# Connectors.net
KiCad netlist of a schematic drawn in Altium Designer
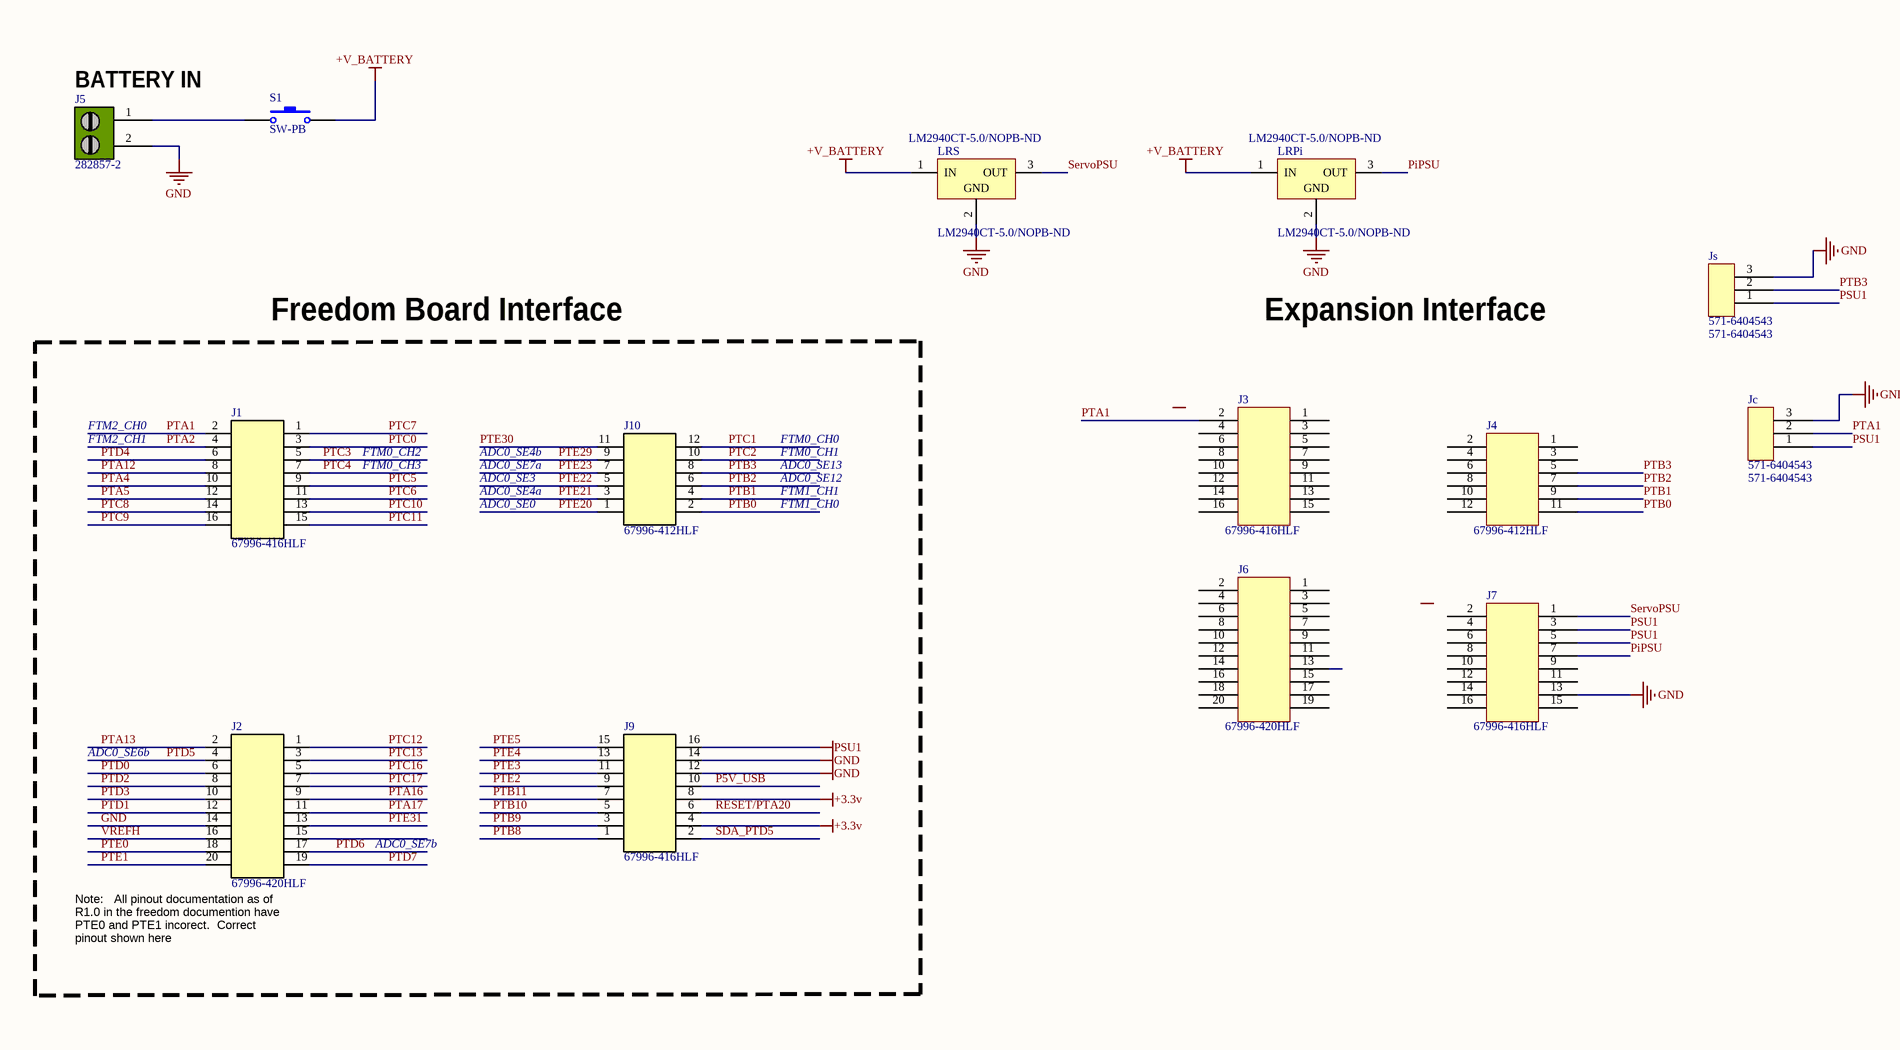
[diagram p0: Connectors.SchDoc, top left]
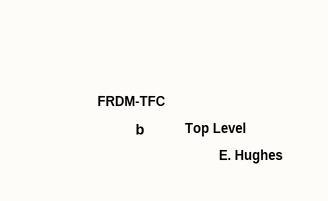
[diagram p1: Connectors.SchDoc, bottom right]

(export (version "E")
  (design (tool "Eeschema 10.0.6"))
  (components
    (comp (ref "J1")
      (value "67996-416HLF")
      (footprint "67996-416HLF")
      (description "CONN HEADER 16POS .100 STR TIN")
      (fields (field (name "MANUFACTURER") "FCI"))
      (libsource (lib "") (part "67996-416HLF_1"))
    )
    (comp (ref "J2")
      (value "67996-420HLF")
      (footprint "67996-420HLF")
      (description "CONN HEADER 20POS .100 STR TIN")
      (fields (field (name "MANUFACTURER") "FCI"))
      (libsource (lib "eConnector") (part "67996-420HLF"))
    )
    (comp (ref "J3")
      (value "67996-416HLF")
      (footprint "67996-416HLF")
      (description "CONN HEADER 16POS .100 STR TIN")
      (libsource (lib "Amphenol_Connectors") (part "67996-416HLF"))
    )
    (comp (ref "J4")
      (value "67996-412HLF")
      (footprint "67996-412HLF")
      (description "CONN HEADER 12POS .100 STR TIN")
      (libsource (lib "Amphenol_Connectors") (part "67996-412HLF"))
    )
    (comp (ref "J5")
      (value "282857-2")
      (footprint "282857-2")
      (description "TERM BLOCK 2POS SIDE ENT 5.08MM")
      (fields (field (name "MANUFACTURER") "TE Connectivity") (field (name "VOLTAGE") "300V"))
      (libsource (lib "eConnector") (part "282857-2"))
    )
    (comp (ref "J6")
      (value "67996-420HLF")
      (footprint "67996-420HLF")
      (description "CONN HEADER 20POS .100 STR TIN")
      (libsource (lib "Amphenol_Connectors") (part "67996-420HLF"))
    )
    (comp (ref "J7")
      (value "67996-416HLF")
      (footprint "67996-416HLF")
      (description "CONN HEADER 16POS .100 STR TIN")
      (libsource (lib "Amphenol_Connectors") (part "67996-416HLF"))
    )
    (comp (ref "J9")
      (value "67996-416HLF")
      (footprint "67996-416HLF")
      (description "CONN HEADER 16POS .100 STR TIN")
      (fields (field (name "MANUFACTURER") "FCI"))
      (libsource (lib "eConnector") (part "67996-416HLF"))
    )
    (comp (ref "J10")
      (value "67996-412HLF")
      (footprint "67996-412HLF")
      (description "CONN HEADER 12POS .100 STR TIN")
      (fields (field (name "MANUFACTURER") "FCI"))
      (libsource (lib "eConnector") (part "67996-412HLF"))
    )
    (comp (ref "Jc")
      (value "571-6404543")
      (footprint "6404543")
      (description "Headers & Wire Housings POLARIZED HEADER 3P Straight Post tin, Mouser")
      (fields (field (name "SUPPLIER PART NUMBER 1") "571-6404543"))
      (libsource (lib "TE_Connectors") (part "640454-3"))
    )
    (comp (ref "Js")
      (value "571-6404543")
      (footprint "6404543")
      (description "Headers & Wire Housings POLARIZED HEADER 3P Straight Post tin, Mouser")
      (fields (field (name "SUPPLIER PART NUMBER 1") "571-6404543"))
      (libsource (lib "TE_Connectors") (part "640454-3"))
    )
    (comp (ref "LRPi")
      (value "LM2940CT-5.0/NOPB-ND")
      (footprint "NDE0003A")
      (description "1A Low Dropout Regulator, 3-pin TO-220, Pb-Free, Digi-key")
      (fields
        (field (name "MANUFACTURER") "Texas Instruments")
        (field (name "SUPPLIER PART NUMBER 1") "LM2940CT-5.0/NOPB-ND")
      )
      (libsource (lib "Altium Content Vault") (part "PM-REG-LM2940-SIL3"))
    )
    (comp (ref "LRS")
      (value "LM2940CT-5.0/NOPB-ND")
      (footprint "NDE0003A")
      (description "1A Low Dropout Regulator, 3-pin TO-220, Pb-Free, Digi-key")
      (fields
        (field (name "MANUFACTURER") "Texas Instruments")
        (field (name "SUPPLIER PART NUMBER 1") "LM2940CT-5.0/NOPB-ND")
      )
      (libsource (lib "Altium Content Vault") (part "PM-REG-LM2940-SIL3"))
    )
    (comp (ref "S1")
      (value "SW-PB")
      (footprint "SPST")
      (description "Switch")
      (fields (field (name "PUBLISHER") "Altium Limited"))
      (libsource (lib "Miscellaneous Devices") (part "SW-PB"))
    )
  )
  (nets
    (net (code "1") (name "+3.3v") (class "Default")
      (node (ref "J9") (pin "4") (pinfunction "4_4") (pintype "passive"))
      (node (ref "J9") (pin "8") (pinfunction "8_8") (pintype "passive"))
    )
    (net (code "2") (name "+V_BATTERY") (class "Default")
      (node (ref "LRPi") (pin "1") (pinfunction "IN_1") (pintype "power_in"))
      (node (ref "LRS") (pin "1") (pinfunction "IN_1") (pintype "power_in"))
      (node (ref "S1") (pin "2") (pinfunction "2_2") (pintype "passive"))
    )
    (net (code "3") (name "/P5V_USB") (class "Default")
      (node (ref "J9") (pin "10") (pinfunction "10_10") (pintype "passive"))
    )
    (net (code "4") (name "/PTA1") (class "Default")
      (node (ref "J1") (pin "2") (pinfunction "2_2") (pintype "passive"))
      (node (ref "J3") (pin "2") (pinfunction "2_2") (pintype "passive"))
      (node (ref "Jc") (pin "2") (pinfunction "2_2") (pintype "passive"))
    )
    (net (code "5") (name "/PTA2") (class "Default")
      (node (ref "J1") (pin "4") (pinfunction "4_4") (pintype "passive"))
    )
    (net (code "6") (name "/PTA4") (class "Default")
      (node (ref "J1") (pin "10") (pinfunction "10_10") (pintype "passive"))
    )
    (net (code "7") (name "/PTA5") (class "Default")
      (node (ref "J1") (pin "12") (pinfunction "12_12") (pintype "passive"))
    )
    (net (code "8") (name "/PTA12") (class "Default")
      (node (ref "J1") (pin "8") (pinfunction "8_8") (pintype "passive"))
    )
    (net (code "9") (name "/PTA13") (class "Default")
      (node (ref "J2") (pin "2") (pinfunction "2_2") (pintype "passive"))
    )
    (net (code "10") (name "/PTA16") (class "Default")
      (node (ref "J2") (pin "9") (pinfunction "9_9") (pintype "passive"))
    )
    (net (code "11") (name "/PTA17") (class "Default")
      (node (ref "J2") (pin "11") (pinfunction "11_11") (pintype "passive"))
    )
    (net (code "12") (name "/PTB0") (class "Default")
      (node (ref "J10") (pin "2") (pinfunction "2_2") (pintype "passive"))
      (node (ref "J4") (pin "11") (pinfunction "11_11") (pintype "passive"))
    )
    (net (code "13") (name "/PTB1") (class "Default")
      (node (ref "J10") (pin "4") (pinfunction "4_4") (pintype "passive"))
      (node (ref "J4") (pin "9") (pinfunction "9_9") (pintype "passive"))
    )
    (net (code "14") (name "/PTB2") (class "Default")
      (node (ref "J10") (pin "6") (pinfunction "6_6") (pintype "passive"))
      (node (ref "J4") (pin "7") (pinfunction "7_7") (pintype "passive"))
    )
    (net (code "15") (name "/PTB3") (class "Default")
      (node (ref "J10") (pin "8") (pinfunction "8_8") (pintype "passive"))
      (node (ref "J4") (pin "5") (pinfunction "5_5") (pintype "passive"))
      (node (ref "Js") (pin "2") (pinfunction "2_2") (pintype "passive"))
    )
    (net (code "16") (name "/PTB8") (class "Default")
      (node (ref "J9") (pin "1") (pinfunction "1_1") (pintype "passive"))
    )
    (net (code "17") (name "/PTB9") (class "Default")
      (node (ref "J9") (pin "3") (pinfunction "3_3") (pintype "passive"))
    )
    (net (code "18") (name "/PTB10") (class "Default")
      (node (ref "J9") (pin "5") (pinfunction "5_5") (pintype "passive"))
    )
    (net (code "19") (name "/PTB11") (class "Default")
      (node (ref "J9") (pin "7") (pinfunction "7_7") (pintype "passive"))
    )
    (net (code "20") (name "/PTC0") (class "Default")
      (node (ref "J1") (pin "3") (pinfunction "3_3") (pintype "passive"))
    )
    (net (code "21") (name "/PTC1") (class "Default")
      (node (ref "J10") (pin "12") (pinfunction "12_12") (pintype "passive"))
    )
    (net (code "22") (name "/PTC2") (class "Default")
      (node (ref "J10") (pin "10") (pinfunction "10_10") (pintype "passive"))
    )
    (net (code "23") (name "/PTC3") (class "Default")
      (node (ref "J1") (pin "5") (pinfunction "5_5") (pintype "passive"))
    )
    (net (code "24") (name "/PTC4") (class "Default")
      (node (ref "J1") (pin "7") (pinfunction "7_7") (pintype "passive"))
    )
    (net (code "25") (name "/PTC5") (class "Default")
      (node (ref "J1") (pin "9") (pinfunction "9_9") (pintype "passive"))
    )
    (net (code "26") (name "/PTC6") (class "Default")
      (node (ref "J1") (pin "11") (pinfunction "11_11") (pintype "passive"))
    )
    (net (code "27") (name "/PTC7") (class "Default")
      (node (ref "J1") (pin "1") (pinfunction "1_1") (pintype "passive"))
    )
    (net (code "28") (name "/PTC8") (class "Default")
      (node (ref "J1") (pin "14") (pinfunction "14_14") (pintype "passive"))
    )
    (net (code "29") (name "/PTC9") (class "Default")
      (node (ref "J1") (pin "16") (pinfunction "16_16") (pintype "passive"))
    )
    (net (code "30") (name "/PTC10") (class "Default")
      (node (ref "J1") (pin "13") (pinfunction "13_13") (pintype "passive"))
    )
    (net (code "31") (name "/PTC11") (class "Default")
      (node (ref "J1") (pin "15") (pinfunction "15_15") (pintype "passive"))
    )
    (net (code "32") (name "/PTC12") (class "Default")
      (node (ref "J2") (pin "1") (pinfunction "1_1") (pintype "passive"))
    )
    (net (code "33") (name "/PTC13") (class "Default")
      (node (ref "J2") (pin "3") (pinfunction "3_3") (pintype "passive"))
    )
    (net (code "34") (name "/PTC16") (class "Default")
      (node (ref "J2") (pin "5") (pinfunction "5_5") (pintype "passive"))
    )
    (net (code "35") (name "/PTC17") (class "Default")
      (node (ref "J2") (pin "7") (pinfunction "7_7") (pintype "passive"))
    )
    (net (code "36") (name "/PTD0") (class "Default")
      (node (ref "J2") (pin "6") (pinfunction "6_6") (pintype "passive"))
    )
    (net (code "37") (name "/PTD1") (class "Default")
      (node (ref "J2") (pin "12") (pinfunction "12_12") (pintype "passive"))
    )
    (net (code "38") (name "/PTD2") (class "Default")
      (node (ref "J2") (pin "8") (pinfunction "8_8") (pintype "passive"))
    )
    (net (code "39") (name "/PTD3") (class "Default")
      (node (ref "J2") (pin "10") (pinfunction "10_10") (pintype "passive"))
    )
    (net (code "40") (name "/PTD4") (class "Default")
      (node (ref "J1") (pin "6") (pinfunction "6_6") (pintype "passive"))
    )
    (net (code "41") (name "/PTD5") (class "Default")
      (node (ref "J2") (pin "4") (pinfunction "4_4") (pintype "passive"))
    )
    (net (code "42") (name "/PTD6") (class "Default")
      (node (ref "J2") (pin "17") (pinfunction "17_17") (pintype "passive"))
    )
    (net (code "43") (name "/PTD7") (class "Default")
      (node (ref "J2") (pin "19") (pinfunction "19_19") (pintype "passive"))
    )
    (net (code "44") (name "/PTE0") (class "Default")
      (node (ref "J2") (pin "18") (pinfunction "18_18") (pintype "passive"))
    )
    (net (code "45") (name "/PTE1") (class "Default")
      (node (ref "J2") (pin "20") (pinfunction "20_20") (pintype "passive"))
    )
    (net (code "46") (name "/PTE2") (class "Default")
      (node (ref "J9") (pin "9") (pinfunction "9_9") (pintype "passive"))
    )
    (net (code "47") (name "/PTE3") (class "Default")
      (node (ref "J9") (pin "11") (pinfunction "11_11") (pintype "passive"))
    )
    (net (code "48") (name "/PTE4") (class "Default")
      (node (ref "J9") (pin "13") (pinfunction "13_13") (pintype "passive"))
    )
    (net (code "49") (name "/PTE5") (class "Default")
      (node (ref "J9") (pin "15") (pinfunction "15_15") (pintype "passive"))
    )
    (net (code "50") (name "/PTE20") (class "Default")
      (node (ref "J10") (pin "1") (pinfunction "1_1") (pintype "passive"))
    )
    (net (code "51") (name "/PTE21") (class "Default")
      (node (ref "J10") (pin "3") (pinfunction "3_3") (pintype "passive"))
    )
    (net (code "52") (name "/PTE22") (class "Default")
      (node (ref "J10") (pin "5") (pinfunction "5_5") (pintype "passive"))
    )
    (net (code "53") (name "/PTE23") (class "Default")
      (node (ref "J10") (pin "7") (pinfunction "7_7") (pintype "passive"))
    )
    (net (code "54") (name "/PTE29") (class "Default")
      (node (ref "J10") (pin "9") (pinfunction "9_9") (pintype "passive"))
    )
    (net (code "55") (name "/PTE30") (class "Default")
      (node (ref "J10") (pin "11") (pinfunction "11_11") (pintype "passive"))
    )
    (net (code "56") (name "/PTE31") (class "Default")
      (node (ref "J2") (pin "13") (pinfunction "13_13") (pintype "passive"))
    )
    (net (code "57") (name "/PiPSU") (class "Default")
      (node (ref "J7") (pin "7") (pinfunction "7_7") (pintype "passive"))
      (node (ref "LRPi") (pin "3") (pinfunction "OUT_3") (pintype "power_in"))
    )
    (net (code "58") (name "/RESET{slash}PTA20") (class "Default")
      (node (ref "J9") (pin "6") (pinfunction "6_6") (pintype "passive"))
    )
    (net (code "59") (name "/SDA_PTD5") (class "Default")
      (node (ref "J9") (pin "2") (pinfunction "2_2") (pintype "passive"))
    )
    (net (code "60") (name "/ServoPSU") (class "Default")
      (node (ref "J7") (pin "1") (pinfunction "1_1") (pintype "passive"))
      (node (ref "LRS") (pin "3") (pinfunction "OUT_3") (pintype "power_in"))
    )
    (net (code "61") (name "/VREFH") (class "Default")
      (node (ref "J2") (pin "16") (pinfunction "16_16") (pintype "passive"))
    )
    (net (code "62") (name "GND") (class "Default")
      (node (ref "J2") (pin "14") (pinfunction "14_14") (pintype "passive"))
      (node (ref "J5") (pin "2") (pinfunction "2_2") (pintype "passive"))
      (node (ref "J7") (pin "13") (pinfunction "13_13") (pintype "passive"))
      (node (ref "J9") (pin "12") (pinfunction "12_12") (pintype "passive"))
      (node (ref "J9") (pin "14") (pinfunction "14_14") (pintype "passive"))
      (node (ref "Jc") (pin "3") (pinfunction "3_3") (pintype "passive"))
      (node (ref "Js") (pin "3") (pinfunction "3_3") (pintype "passive"))
      (node (ref "LRPi") (pin "2") (pinfunction "GND_2") (pintype "power_in"))
      (node (ref "LRS") (pin "2") (pinfunction "GND_2") (pintype "power_in"))
    )
    (net (code "63") (name "Net-(J5-Pad1)") (class "Default")
      (node (ref "J5") (pin "1") (pinfunction "1_1") (pintype "passive"))
      (node (ref "S1") (pin "1") (pinfunction "1_1") (pintype "passive"))
    )
    (net (code "64") (name "PSU1") (class "Default")
      (node (ref "J7") (pin "3") (pinfunction "3_3") (pintype "passive"))
      (node (ref "J7") (pin "5") (pinfunction "5_5") (pintype "passive"))
      (node (ref "J9") (pin "16") (pinfunction "16_16") (pintype "passive"))
      (node (ref "Jc") (pin "1") (pinfunction "1_1") (pintype "passive"))
      (node (ref "Js") (pin "1") (pinfunction "1_1") (pintype "passive"))
    )
    (net (code "65") (name "unconnected-(J2-Pad15)") (class "Default")
      (node (ref "J2") (pin "15") (pinfunction "15_15") (pintype "passive"))
    )
    (net (code "66") (name "unconnected-(J3-Pad1)") (class "Default")
      (node (ref "J3") (pin "1") (pinfunction "1_1") (pintype "passive"))
    )
    (net (code "67") (name "unconnected-(J3-Pad3)") (class "Default")
      (node (ref "J3") (pin "3") (pinfunction "3_3") (pintype "passive"))
    )
    (net (code "68") (name "unconnected-(J3-Pad4)") (class "Default")
      (node (ref "J3") (pin "4") (pinfunction "4_4") (pintype "passive"))
    )
    (net (code "69") (name "unconnected-(J3-Pad5)") (class "Default")
      (node (ref "J3") (pin "5") (pinfunction "5_5") (pintype "passive"))
    )
    (net (code "70") (name "unconnected-(J3-Pad6)") (class "Default")
      (node (ref "J3") (pin "6") (pinfunction "6_6") (pintype "passive"))
    )
    (net (code "71") (name "unconnected-(J3-Pad7)") (class "Default")
      (node (ref "J3") (pin "7") (pinfunction "7_7") (pintype "passive"))
    )
    (net (code "72") (name "unconnected-(J3-Pad8)") (class "Default")
      (node (ref "J3") (pin "8") (pinfunction "8_8") (pintype "passive"))
    )
    (net (code "73") (name "unconnected-(J3-Pad9)") (class "Default")
      (node (ref "J3") (pin "9") (pinfunction "9_9") (pintype "passive"))
    )
    (net (code "74") (name "unconnected-(J3-Pad10)") (class "Default")
      (node (ref "J3") (pin "10") (pinfunction "10_10") (pintype "passive"))
    )
    (net (code "75") (name "unconnected-(J3-Pad11)") (class "Default")
      (node (ref "J3") (pin "11") (pinfunction "11_11") (pintype "passive"))
    )
    (net (code "76") (name "unconnected-(J3-Pad12)") (class "Default")
      (node (ref "J3") (pin "12") (pinfunction "12_12") (pintype "passive"))
    )
    (net (code "77") (name "unconnected-(J3-Pad13)") (class "Default")
      (node (ref "J3") (pin "13") (pinfunction "13_13") (pintype "passive"))
    )
    (net (code "78") (name "unconnected-(J3-Pad14)") (class "Default")
      (node (ref "J3") (pin "14") (pinfunction "14_14") (pintype "passive"))
    )
    (net (code "79") (name "unconnected-(J3-Pad15)") (class "Default")
      (node (ref "J3") (pin "15") (pinfunction "15_15") (pintype "passive"))
    )
    (net (code "80") (name "unconnected-(J3-Pad16)") (class "Default")
      (node (ref "J3") (pin "16") (pinfunction "16_16") (pintype "passive"))
    )
    (net (code "81") (name "unconnected-(J4-Pad1)") (class "Default")
      (node (ref "J4") (pin "1") (pinfunction "1_1") (pintype "passive"))
    )
    (net (code "82") (name "unconnected-(J4-Pad2)") (class "Default")
      (node (ref "J4") (pin "2") (pinfunction "2_2") (pintype "passive"))
    )
    (net (code "83") (name "unconnected-(J4-Pad3)") (class "Default")
      (node (ref "J4") (pin "3") (pinfunction "3_3") (pintype "passive"))
    )
    (net (code "84") (name "unconnected-(J4-Pad4)") (class "Default")
      (node (ref "J4") (pin "4") (pinfunction "4_4") (pintype "passive"))
    )
    (net (code "85") (name "unconnected-(J4-Pad6)") (class "Default")
      (node (ref "J4") (pin "6") (pinfunction "6_6") (pintype "passive"))
    )
    (net (code "86") (name "unconnected-(J4-Pad8)") (class "Default")
      (node (ref "J4") (pin "8") (pinfunction "8_8") (pintype "passive"))
    )
    (net (code "87") (name "unconnected-(J4-Pad10)") (class "Default")
      (node (ref "J4") (pin "10") (pinfunction "10_10") (pintype "passive"))
    )
    (net (code "88") (name "unconnected-(J4-Pad12)") (class "Default")
      (node (ref "J4") (pin "12") (pinfunction "12_12") (pintype "passive"))
    )
    (net (code "89") (name "unconnected-(J6-Pad1)") (class "Default")
      (node (ref "J6") (pin "1") (pinfunction "1_1") (pintype "passive"))
    )
    (net (code "90") (name "unconnected-(J6-Pad2)") (class "Default")
      (node (ref "J6") (pin "2") (pinfunction "2_2") (pintype "passive"))
    )
    (net (code "91") (name "unconnected-(J6-Pad3)") (class "Default")
      (node (ref "J6") (pin "3") (pinfunction "3_3") (pintype "passive"))
    )
    (net (code "92") (name "unconnected-(J6-Pad4)") (class "Default")
      (node (ref "J6") (pin "4") (pinfunction "4_4") (pintype "passive"))
    )
    (net (code "93") (name "unconnected-(J6-Pad5)") (class "Default")
      (node (ref "J6") (pin "5") (pinfunction "5_5") (pintype "passive"))
    )
    (net (code "94") (name "unconnected-(J6-Pad6)") (class "Default")
      (node (ref "J6") (pin "6") (pinfunction "6_6") (pintype "passive"))
    )
    (net (code "95") (name "unconnected-(J6-Pad7)") (class "Default")
      (node (ref "J6") (pin "7") (pinfunction "7_7") (pintype "passive"))
    )
    (net (code "96") (name "unconnected-(J6-Pad8)") (class "Default")
      (node (ref "J6") (pin "8") (pinfunction "8_8") (pintype "passive"))
    )
    (net (code "97") (name "unconnected-(J6-Pad9)") (class "Default")
      (node (ref "J6") (pin "9") (pinfunction "9_9") (pintype "passive"))
    )
    (net (code "98") (name "unconnected-(J6-Pad10)") (class "Default")
      (node (ref "J6") (pin "10") (pinfunction "10_10") (pintype "passive"))
    )
    (net (code "99") (name "unconnected-(J6-Pad11)") (class "Default")
      (node (ref "J6") (pin "11") (pinfunction "11_11") (pintype "passive"))
    )
    (net (code "100") (name "unconnected-(J6-Pad12)") (class "Default")
      (node (ref "J6") (pin "12") (pinfunction "12_12") (pintype "passive"))
    )
    (net (code "101") (name "unconnected-(J6-Pad13)") (class "Default")
      (node (ref "J6") (pin "13") (pinfunction "13_13") (pintype "passive"))
    )
    (net (code "102") (name "unconnected-(J6-Pad14)") (class "Default")
      (node (ref "J6") (pin "14") (pinfunction "14_14") (pintype "passive"))
    )
    (net (code "103") (name "unconnected-(J6-Pad15)") (class "Default")
      (node (ref "J6") (pin "15") (pinfunction "15_15") (pintype "passive"))
    )
    (net (code "104") (name "unconnected-(J6-Pad16)") (class "Default")
      (node (ref "J6") (pin "16") (pinfunction "16_16") (pintype "passive"))
    )
    (net (code "105") (name "unconnected-(J6-Pad17)") (class "Default")
      (node (ref "J6") (pin "17") (pinfunction "17_17") (pintype "passive"))
    )
    (net (code "106") (name "unconnected-(J6-Pad18)") (class "Default")
      (node (ref "J6") (pin "18") (pinfunction "18_18") (pintype "passive"))
    )
    (net (code "107") (name "unconnected-(J6-Pad19)") (class "Default")
      (node (ref "J6") (pin "19") (pinfunction "19_19") (pintype "passive"))
    )
    (net (code "108") (name "unconnected-(J6-Pad20)") (class "Default")
      (node (ref "J6") (pin "20") (pinfunction "20_20") (pintype "passive"))
    )
    (net (code "109") (name "unconnected-(J7-Pad2)") (class "Default")
      (node (ref "J7") (pin "2") (pinfunction "2_2") (pintype "passive"))
    )
    (net (code "110") (name "unconnected-(J7-Pad4)") (class "Default")
      (node (ref "J7") (pin "4") (pinfunction "4_4") (pintype "passive"))
    )
    (net (code "111") (name "unconnected-(J7-Pad6)") (class "Default")
      (node (ref "J7") (pin "6") (pinfunction "6_6") (pintype "passive"))
    )
    (net (code "112") (name "unconnected-(J7-Pad8)") (class "Default")
      (node (ref "J7") (pin "8") (pinfunction "8_8") (pintype "passive"))
    )
    (net (code "113") (name "unconnected-(J7-Pad9)") (class "Default")
      (node (ref "J7") (pin "9") (pinfunction "9_9") (pintype "passive"))
    )
    (net (code "114") (name "unconnected-(J7-Pad10)") (class "Default")
      (node (ref "J7") (pin "10") (pinfunction "10_10") (pintype "passive"))
    )
    (net (code "115") (name "unconnected-(J7-Pad11)") (class "Default")
      (node (ref "J7") (pin "11") (pinfunction "11_11") (pintype "passive"))
    )
    (net (code "116") (name "unconnected-(J7-Pad12)") (class "Default")
      (node (ref "J7") (pin "12") (pinfunction "12_12") (pintype "passive"))
    )
    (net (code "117") (name "unconnected-(J7-Pad14)") (class "Default")
      (node (ref "J7") (pin "14") (pinfunction "14_14") (pintype "passive"))
    )
    (net (code "118") (name "unconnected-(J7-Pad15)") (class "Default")
      (node (ref "J7") (pin "15") (pinfunction "15_15") (pintype "passive"))
    )
    (net (code "119") (name "unconnected-(J7-Pad16)") (class "Default")
      (node (ref "J7") (pin "16") (pinfunction "16_16") (pintype "passive"))
    )
  )
)
